# Power_Controller.net
KiCad netlist of a schematic drawn in Altium Designer
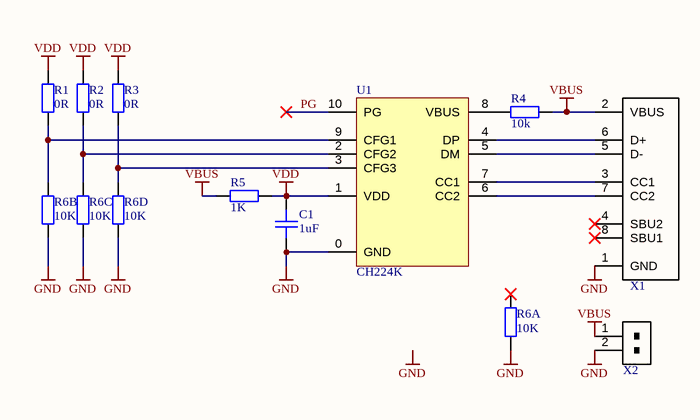
[diagram p0: Power Controller.SchDoc]

(export (version "E")
  (design (tool "Eeschema 10.0.6"))
  (components
    (comp (ref "C1")
      (value "1uF")
      (footprint "CAP-0805")
      (description "Capacitor Non-Polar")
      (fields (field (name "TOLERANCE") "X7R") (field (name "VOLTAGE") "50V"))
      (libsource (lib "HW_components") (part "CAP-0805"))
    )
    (comp (ref "MH1")
      (value "MECH-SCREW")
      (footprint "MECH-M2-LARGE-EMPTY-NORMAL-SUPPORT")
      (description "M2, large ring, normal support silkscreen")
      (libsource (lib "HW_components") (part "MECH-SCREW"))
    )
    (comp (ref "R1")
      (value "0R")
      (footprint "RES-0603")
      (description "Resistor")
      (libsource (lib "HW_components") (part "RES-0603"))
    )
    (comp (ref "R2")
      (value "0R")
      (footprint "RES-0603")
      (description "Resistor")
      (libsource (lib "HW_components") (part "RES-0603"))
    )
    (comp (ref "R3")
      (value "0R")
      (footprint "RES-0603")
      (description "Resistor")
      (libsource (lib "HW_components") (part "RES-0603"))
    )
    (comp (ref "R4")
      (value "10k")
      (footprint "RES-0603")
      (description "Resistor")
      (libsource (lib "") (part "RES-0603_1"))
    )
    (comp (ref "R5")
      (value "1K")
      (footprint "RES-0603")
      (description "Resistor")
      (libsource (lib "") (part "RES-0603_2"))
    )
    (comp (ref "R6")
      (value "10K")
      (footprint "RES-ARRAY-1206")
      (description "4x resistor array")
      (libsource (lib "HW_components") (part "RES-ARRAY"))
    )
    (comp (ref "U1")
      (value "CH224K")
      (footprint "IC-TSSOP-10-TP")
      (description "USB PD and Other Fast Charging Protocol Sink Controller")
      (libsource (lib "HW_components") (part "IC-POWER-CH224K"))
    )
    (comp (ref "X1")
      (value "CONN-USB-C-DATA")
      (footprint "CONN-USB-C-DATA")
      (description "Csatlakozó, USB C, 5V, 5A, 16 pin, SMD")
      (libsource (lib "HW_components") (part "CONN-USB-C-DATA"))
    )
    (comp (ref "X2")
      (value "CONN-2P")
      (footprint "CONN-2P-JST-2.0MM-RIGHT")
      (description "TÁPCSATL. 2.00mm 2P APA 90° NCW200S-02R (G-S) FORR.")
      (libsource (lib "HW_components") (part "CONN-2P"))
    )
  )
  (nets
    (net (code "1") (name "/PG") (class "Default")
      (node (ref "U1") (pin "10") (pinfunction "PG_10") (pintype "passive+no_connect"))
    )
    (net (code "2") (name "GND") (class "Default")
      (node (ref "C1") (pin "1") (pinfunction "1_1") (pintype "passive"))
      (node (ref "MH1") (pin "MH") (pinfunction "Con_MH") (pintype "passive"))
      (node (ref "R6") (pin "1") (pinfunction "1_1") (pintype "passive"))
      (node (ref "R6") (pin "2") (pinfunction "2_2") (pintype "passive"))
      (node (ref "R6") (pin "3") (pinfunction "3_3") (pintype "passive"))
      (node (ref "R6") (pin "4") (pinfunction "4_4") (pintype "passive"))
      (node (ref "U1") (pin "0") (pinfunction "GND_0") (pintype "passive"))
      (node (ref "X1") (pin "1") (pinfunction "GND_1") (pintype "passive"))
      (node (ref "X2") (pin "2") (pinfunction "2_2") (pintype "passive"))
    )
    (net (code "3") (name "Net-(U1-CC1)") (class "Default")
      (node (ref "U1") (pin "7") (pinfunction "CC1_7") (pintype "passive"))
      (node (ref "X1") (pin "3") (pinfunction "CC1_3") (pintype "passive"))
    )
    (net (code "4") (name "Net-(U1-CC2)") (class "Default")
      (node (ref "U1") (pin "6") (pinfunction "CC2_6") (pintype "passive"))
      (node (ref "X1") (pin "7") (pinfunction "CC2_7") (pintype "passive"))
    )
    (net (code "5") (name "Net-(U1-CFG1)") (class "Default")
      (node (ref "R1") (pin "1") (pinfunction "1_1") (pintype "passive"))
      (node (ref "R6") (pin "7") (pinfunction "7_7") (pintype "passive"))
      (node (ref "U1") (pin "9") (pinfunction "CFG1_9") (pintype "passive"))
    )
    (net (code "6") (name "Net-(U1-CFG2)") (class "Default")
      (node (ref "R2") (pin "1") (pinfunction "1_1") (pintype "passive"))
      (node (ref "R6") (pin "6") (pinfunction "6_6") (pintype "passive"))
      (node (ref "U1") (pin "2") (pinfunction "CFG2_2") (pintype "passive"))
    )
    (net (code "7") (name "Net-(U1-CFG3)") (class "Default")
      (node (ref "R3") (pin "1") (pinfunction "1_1") (pintype "passive"))
      (node (ref "R6") (pin "5") (pinfunction "5_5") (pintype "passive"))
      (node (ref "U1") (pin "3") (pinfunction "CFG3_3") (pintype "passive"))
    )
    (net (code "8") (name "Net-(U1-DM)") (class "Default")
      (node (ref "U1") (pin "5") (pinfunction "DM_5") (pintype "passive"))
      (node (ref "X1") (pin "5") (pinfunction "D-_5") (pintype "passive"))
    )
    (net (code "9") (name "Net-(U1-DP)") (class "Default")
      (node (ref "U1") (pin "4") (pinfunction "DP_4") (pintype "passive"))
      (node (ref "X1") (pin "6") (pinfunction "D+_6") (pintype "passive"))
    )
    (net (code "10") (name "Net-(U1-VBUS)") (class "Default")
      (node (ref "R4") (pin "2") (pinfunction "2_2") (pintype "passive"))
      (node (ref "U1") (pin "8") (pinfunction "VBUS_8") (pintype "passive"))
    )
    (net (code "11") (name "VBUS") (class "Default")
      (node (ref "R4") (pin "1") (pinfunction "1_1") (pintype "passive"))
      (node (ref "R5") (pin "1") (pinfunction "1_1") (pintype "passive"))
      (node (ref "X1") (pin "2") (pinfunction "VBUS_2") (pintype "passive"))
      (node (ref "X2") (pin "1") (pinfunction "1_1") (pintype "passive"))
    )
    (net (code "12") (name "VDD") (class "Default")
      (node (ref "C1") (pin "2") (pinfunction "2_2") (pintype "passive"))
      (node (ref "R1") (pin "2") (pinfunction "2_2") (pintype "passive"))
      (node (ref "R2") (pin "2") (pinfunction "2_2") (pintype "passive"))
      (node (ref "R3") (pin "2") (pinfunction "2_2") (pintype "passive"))
      (node (ref "R5") (pin "2") (pinfunction "2_2") (pintype "passive"))
      (node (ref "U1") (pin "1") (pinfunction "VDD_1") (pintype "passive"))
    )
    (net (code "13") (name "unconnected-(R6-Pad8)") (class "Default")
      (node (ref "R6") (pin "8") (pinfunction "8_8") (pintype "passive+no_connect"))
    )
    (net (code "14") (name "unconnected-(X1-SBU1-Pad8)") (class "Default")
      (node (ref "X1") (pin "8") (pinfunction "SBU1_8") (pintype "passive+no_connect"))
    )
    (net (code "15") (name "unconnected-(X1-SBU2-Pad4)") (class "Default")
      (node (ref "X1") (pin "4") (pinfunction "SBU2_4") (pintype "passive+no_connect"))
    )
  )
)
